# WRO_2025.net
KiCad netlist of a schematic drawn in EAGLE
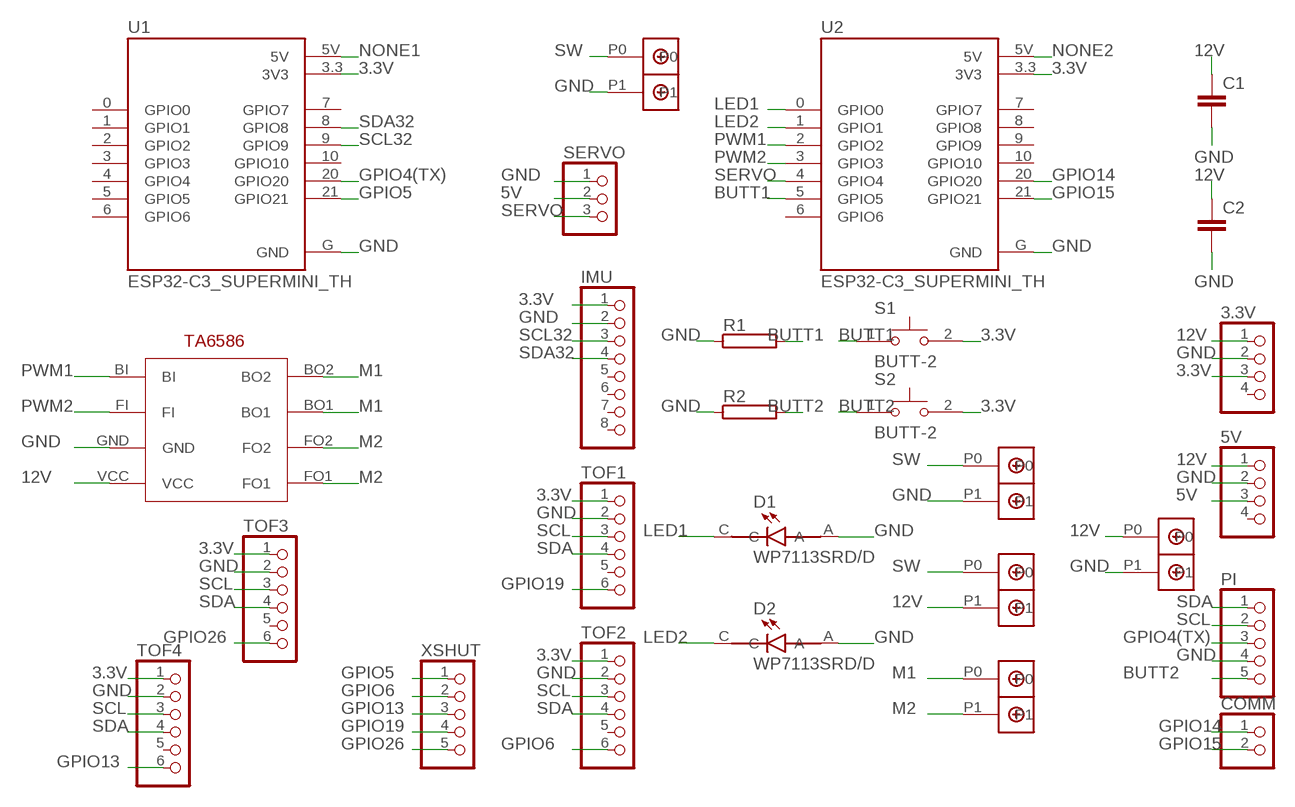
[diagram p0: schematic, sheet 1]

(export (version "E")
  (design (tool "Eeschema 10.0.6"))
  (components
    (comp (ref "3.3V")
      (value "PINHD-1X4")
      (footprint "eagle-import:1X04")
      (libsource (lib "eagle-import") (part "PINHD-1X4"))
    )
    (comp (ref "5V")
      (value "PINHD-1X4")
      (footprint "eagle-import:1X04")
      (libsource (lib "eagle-import") (part "PINHD-1X4"))
    )
    (comp (ref "C1")
      (value "C2,5-3")
      (footprint "eagle-import:C2.5-3")
      (libsource (lib "eagle-import") (part "C2,5-3"))
    )
    (comp (ref "C2")
      (value "C2,5-3")
      (footprint "eagle-import:C2.5-3")
      (libsource (lib "eagle-import") (part "C2,5-3"))
    )
    (comp (ref "COMM")
      (value "PINHD-1X2")
      (footprint "eagle-import:1X02")
      (libsource (lib "eagle-import") (part "PINHD-1X2"))
    )
    (comp (ref "D1")
      (value "WP7113SRD/D")
      (footprint "eagle-import:LED_WP7113SRD_D")
      (fields (field (name "MF") "Kingbright"))
      (libsource (lib "eagle-import") (part "WP7113SRD/D"))
    )
    (comp (ref "D2")
      (value "WP7113SRD/D")
      (footprint "eagle-import:LED_WP7113SRD_D")
      (fields (field (name "MF") "Kingbright"))
      (libsource (lib "eagle-import") (part "WP7113SRD/D"))
    )
    (comp (ref "IMU")
      (value "PINHD-1X8")
      (footprint "eagle-import:1X08")
      (libsource (lib "eagle-import") (part "PINHD-1X8"))
    )
    (comp (ref "PI")
      (value "PINHD-1X5")
      (footprint "eagle-import:1X05")
      (libsource (lib "eagle-import") (part "PINHD-1X5"))
    )
    (comp (ref "R1")
      (value "RHPS58")
      (footprint "eagle-import:HPS58")
      (libsource (lib "eagle-import") (part "RHPS58"))
    )
    (comp (ref "R2")
      (value "RHPS58")
      (footprint "eagle-import:HPS58")
      (libsource (lib "eagle-import") (part "RHPS58"))
    )
    (comp (ref "S1")
      (value "BUTT-2")
      (footprint "eagle-import:SW_BUTT-2")
      (fields (field (name "MF") "Gravitech"))
      (libsource (lib "eagle-import") (part "BUTT-2"))
    )
    (comp (ref "S2")
      (value "BUTT-2")
      (footprint "eagle-import:SW_BUTT-2")
      (fields (field (name "MF") "Gravitech"))
      (libsource (lib "eagle-import") (part "BUTT-2"))
    )
    (comp (ref "SERVO")
      (value "PINHD-1X3")
      (footprint "eagle-import:1X03")
      (libsource (lib "eagle-import") (part "PINHD-1X3"))
    )
    (comp (ref "TOF1")
      (value "PINHD-1X6")
      (footprint "eagle-import:1X06")
      (libsource (lib "eagle-import") (part "PINHD-1X6"))
    )
    (comp (ref "TOF2")
      (value "PINHD-1X6")
      (footprint "eagle-import:1X06")
      (libsource (lib "eagle-import") (part "PINHD-1X6"))
    )
    (comp (ref "TOF3")
      (value "PINHD-1X6")
      (footprint "eagle-import:1X06")
      (libsource (lib "eagle-import") (part "PINHD-1X6"))
    )
    (comp (ref "TOF4")
      (value "PINHD-1X6")
      (footprint "eagle-import:1X06")
      (libsource (lib "eagle-import") (part "PINHD-1X6"))
    )
    (comp (ref "U$1")
      (value "DBCONN-1X2")
      (footprint "eagle-import:DBCONN-1X2")
      (libsource (lib "eagle-import") (part "DBCONN-1X2"))
    )
    (comp (ref "U$2")
      (value "DBCONN-1X2")
      (footprint "eagle-import:DBCONN-1X2")
      (libsource (lib "eagle-import") (part "DBCONN-1X2"))
    )
    (comp (ref "U$3")
      (value "DBCONN-1X2")
      (footprint "eagle-import:DBCONN-1X2")
      (libsource (lib "eagle-import") (part "DBCONN-1X2"))
    )
    (comp (ref "U$4")
      (value "TA6586")
      (footprint "eagle-import:TA6586-FOOTPRINT")
      (fields (field (name "MF") "Wuxi"))
      (libsource (lib "eagle-import") (part "TA6586"))
    )
    (comp (ref "U$5")
      (value "DBCONN-1X2")
      (footprint "eagle-import:DBCONN-1X2")
      (libsource (lib "eagle-import") (part "DBCONN-1X2"))
    )
    (comp (ref "U$6")
      (value "DBCONN-1X2")
      (footprint "eagle-import:DBCONN-1X2")
      (libsource (lib "eagle-import") (part "DBCONN-1X2"))
    )
    (comp (ref "U1")
      (value "ESP32-C3_SUPERMINI_TH")
      (footprint "eagle-import:MODULE_ESP32-C3_SUPERMINI_TH")
      (fields (field (name "MF") "Espressif Systems") (field (name "MP") "ESP32-C3 SuperMini_TH"))
      (libsource (lib "eagle-import") (part "ESP32-C3_SUPERMINI_TH"))
    )
    (comp (ref "U2")
      (value "ESP32-C3_SUPERMINI_TH")
      (footprint "eagle-import:MODULE_ESP32-C3_SUPERMINI_TH")
      (fields (field (name "MF") "Espressif Systems") (field (name "MP") "ESP32-C3 SuperMini_TH"))
      (libsource (lib "eagle-import") (part "ESP32-C3_SUPERMINI_TH"))
    )
    (comp (ref "XSHUT")
      (value "PINHD-1X5")
      (footprint "eagle-import:1X05")
      (libsource (lib "eagle-import") (part "PINHD-1X5"))
    )
  )
  (nets
    (net (code "1") (name "/3.3V") (class "Default")
      (node (ref "3.3V") (pin "3") (pinfunction "3_3") (pintype "passive"))
      (node (ref "IMU") (pin "1") (pinfunction "1_1") (pintype "passive"))
      (node (ref "S1") (pin "2") (pinfunction "2_2") (pintype "passive"))
      (node (ref "S2") (pin "2") (pinfunction "2_2") (pintype "passive"))
      (node (ref "TOF1") (pin "1") (pinfunction "1_1") (pintype "passive"))
      (node (ref "TOF2") (pin "1") (pinfunction "1_1") (pintype "passive"))
      (node (ref "TOF3") (pin "1") (pinfunction "1_1") (pintype "passive"))
      (node (ref "TOF4") (pin "1") (pinfunction "1_1") (pintype "passive"))
      (node (ref "U1") (pin "3.3") (pinfunction "3V3_3.3") (pintype "power_in"))
      (node (ref "U2") (pin "3.3") (pinfunction "3V3_3.3") (pintype "power_in"))
    )
    (net (code "2") (name "/5V") (class "Default")
      (node (ref "5V") (pin "3") (pinfunction "3_3") (pintype "passive"))
      (node (ref "SERVO") (pin "2") (pinfunction "2_2") (pintype "passive"))
    )
    (net (code "3") (name "/12V") (class "Default")
      (node (ref "3.3V") (pin "1") (pinfunction "1_1") (pintype "passive"))
      (node (ref "5V") (pin "1") (pinfunction "1_1") (pintype "passive"))
      (node (ref "C1") (pin "1") (pinfunction "1_1") (pintype "passive"))
      (node (ref "C2") (pin "1") (pinfunction "1_1") (pintype "passive"))
      (node (ref "U$2") (pin "P1") (pinfunction "P1_P1") (pintype "bidirectional"))
      (node (ref "U$4") (pin "VCC") (pinfunction "VCC_VCC") (pintype "bidirectional"))
      (node (ref "U$5") (pin "P0") (pinfunction "P0_P0") (pintype "bidirectional"))
    )
    (net (code "4") (name "/BUTT1") (class "Default")
      (node (ref "R1") (pin "2") (pinfunction "2_2") (pintype "passive"))
      (node (ref "S1") (pin "1") (pinfunction "1_1") (pintype "passive"))
      (node (ref "U2") (pin "5") (pinfunction "GPIO5_5") (pintype "bidirectional"))
    )
    (net (code "5") (name "/BUTT2") (class "Default")
      (node (ref "PI") (pin "5") (pinfunction "5_5") (pintype "passive"))
      (node (ref "R2") (pin "2") (pinfunction "2_2") (pintype "passive"))
      (node (ref "S2") (pin "1") (pinfunction "1_1") (pintype "passive"))
    )
    (net (code "6") (name "/GND") (class "Default")
      (node (ref "3.3V") (pin "2") (pinfunction "2_2") (pintype "passive"))
      (node (ref "5V") (pin "2") (pinfunction "2_2") (pintype "passive"))
      (node (ref "C1") (pin "2") (pinfunction "2_2") (pintype "passive"))
      (node (ref "C2") (pin "2") (pinfunction "2_2") (pintype "passive"))
      (node (ref "D1") (pin "A") (pinfunction "A_A") (pintype "passive"))
      (node (ref "D2") (pin "A") (pinfunction "A_A") (pintype "passive"))
      (node (ref "IMU") (pin "2") (pinfunction "2_2") (pintype "passive"))
      (node (ref "PI") (pin "4") (pinfunction "4_4") (pintype "passive"))
      (node (ref "R1") (pin "1") (pinfunction "1_1") (pintype "passive"))
      (node (ref "R2") (pin "1") (pinfunction "1_1") (pintype "passive"))
      (node (ref "SERVO") (pin "1") (pinfunction "1_1") (pintype "passive"))
      (node (ref "TOF1") (pin "2") (pinfunction "2_2") (pintype "passive"))
      (node (ref "TOF2") (pin "2") (pinfunction "2_2") (pintype "passive"))
      (node (ref "TOF3") (pin "2") (pinfunction "2_2") (pintype "passive"))
      (node (ref "TOF4") (pin "2") (pinfunction "2_2") (pintype "passive"))
      (node (ref "U$1") (pin "P1") (pinfunction "P1_P1") (pintype "bidirectional"))
      (node (ref "U$4") (pin "GND") (pinfunction "GND_GND") (pintype "bidirectional"))
      (node (ref "U$5") (pin "P1") (pinfunction "P1_P1") (pintype "bidirectional"))
      (node (ref "U$6") (pin "P1") (pinfunction "P1_P1") (pintype "bidirectional"))
      (node (ref "U1") (pin "G") (pinfunction "GND_G") (pintype "power_in"))
      (node (ref "U2") (pin "G") (pinfunction "GND_G") (pintype "power_in"))
    )
    (net (code "7") (name "/GPIO4(TX)") (class "Default")
      (node (ref "PI") (pin "3") (pinfunction "3_3") (pintype "passive"))
      (node (ref "U1") (pin "20") (pinfunction "GPIO20_20") (pintype "bidirectional"))
    )
    (net (code "8") (name "/GPIO5") (class "Default")
      (node (ref "U1") (pin "21") (pinfunction "GPIO21_21") (pintype "bidirectional"))
      (node (ref "XSHUT") (pin "1") (pinfunction "1_1") (pintype "passive"))
    )
    (net (code "9") (name "/GPIO6") (class "Default")
      (node (ref "TOF2") (pin "6") (pinfunction "6_6") (pintype "passive"))
      (node (ref "XSHUT") (pin "2") (pinfunction "2_2") (pintype "passive"))
    )
    (net (code "10") (name "/GPIO13") (class "Default")
      (node (ref "TOF4") (pin "6") (pinfunction "6_6") (pintype "passive"))
      (node (ref "XSHUT") (pin "3") (pinfunction "3_3") (pintype "passive"))
    )
    (net (code "11") (name "/GPIO14") (class "Default")
      (node (ref "COMM") (pin "1") (pinfunction "1_1") (pintype "passive"))
      (node (ref "U2") (pin "20") (pinfunction "GPIO20_20") (pintype "bidirectional"))
    )
    (net (code "12") (name "/GPIO15") (class "Default")
      (node (ref "COMM") (pin "2") (pinfunction "2_2") (pintype "passive"))
      (node (ref "U2") (pin "21") (pinfunction "GPIO21_21") (pintype "bidirectional"))
    )
    (net (code "13") (name "/GPIO19") (class "Default")
      (node (ref "TOF1") (pin "6") (pinfunction "6_6") (pintype "passive"))
      (node (ref "XSHUT") (pin "4") (pinfunction "4_4") (pintype "passive"))
    )
    (net (code "14") (name "/GPIO26") (class "Default")
      (node (ref "TOF3") (pin "6") (pinfunction "6_6") (pintype "passive"))
      (node (ref "XSHUT") (pin "5") (pinfunction "5_5") (pintype "passive"))
    )
    (net (code "15") (name "/LED1") (class "Default")
      (node (ref "D1") (pin "C") (pinfunction "C_C") (pintype "passive"))
      (node (ref "U2") (pin "0") (pinfunction "GPIO0_0") (pintype "bidirectional"))
    )
    (net (code "16") (name "/LED2") (class "Default")
      (node (ref "D2") (pin "C") (pinfunction "C_C") (pintype "passive"))
      (node (ref "U2") (pin "1") (pinfunction "GPIO1_1") (pintype "bidirectional"))
    )
    (net (code "17") (name "/M1") (class "Default")
      (node (ref "U$3") (pin "P0") (pinfunction "P0_P0") (pintype "bidirectional"))
      (node (ref "U$4") (pin "BO1") (pinfunction "BO1_BO1") (pintype "bidirectional"))
      (node (ref "U$4") (pin "BO2") (pinfunction "BO2_BO2") (pintype "bidirectional"))
    )
    (net (code "18") (name "/M2") (class "Default")
      (node (ref "U$3") (pin "P1") (pinfunction "P1_P1") (pintype "bidirectional"))
      (node (ref "U$4") (pin "FO1") (pinfunction "FO1_FO1") (pintype "bidirectional"))
      (node (ref "U$4") (pin "FO2") (pinfunction "FO2_FO2") (pintype "bidirectional"))
    )
    (net (code "19") (name "/NONE1") (class "Default")
      (node (ref "U1") (pin "5V") (pinfunction "5V_5V") (pintype "power_in"))
    )
    (net (code "20") (name "/NONE2") (class "Default")
      (node (ref "U2") (pin "5V") (pinfunction "5V_5V") (pintype "power_in"))
    )
    (net (code "21") (name "/PWM1") (class "Default")
      (node (ref "U$4") (pin "BI") (pinfunction "BI_BI") (pintype "bidirectional"))
      (node (ref "U2") (pin "2") (pinfunction "GPIO2_2") (pintype "bidirectional"))
    )
    (net (code "22") (name "/PWM2") (class "Default")
      (node (ref "U$4") (pin "FI") (pinfunction "FI_FI") (pintype "bidirectional"))
      (node (ref "U2") (pin "3") (pinfunction "GPIO3_3") (pintype "bidirectional"))
    )
    (net (code "23") (name "/SCL") (class "Default")
      (node (ref "PI") (pin "2") (pinfunction "2_2") (pintype "passive"))
      (node (ref "TOF1") (pin "3") (pinfunction "3_3") (pintype "passive"))
      (node (ref "TOF2") (pin "3") (pinfunction "3_3") (pintype "passive"))
      (node (ref "TOF3") (pin "3") (pinfunction "3_3") (pintype "passive"))
      (node (ref "TOF4") (pin "3") (pinfunction "3_3") (pintype "passive"))
    )
    (net (code "24") (name "/SCL32") (class "Default")
      (node (ref "IMU") (pin "3") (pinfunction "3_3") (pintype "passive"))
      (node (ref "U1") (pin "9") (pinfunction "GPIO9_9") (pintype "bidirectional"))
    )
    (net (code "25") (name "/SDA") (class "Default")
      (node (ref "PI") (pin "1") (pinfunction "1_1") (pintype "passive"))
      (node (ref "TOF1") (pin "4") (pinfunction "4_4") (pintype "passive"))
      (node (ref "TOF2") (pin "4") (pinfunction "4_4") (pintype "passive"))
      (node (ref "TOF3") (pin "4") (pinfunction "4_4") (pintype "passive"))
      (node (ref "TOF4") (pin "4") (pinfunction "4_4") (pintype "passive"))
    )
    (net (code "26") (name "/SDA32") (class "Default")
      (node (ref "IMU") (pin "4") (pinfunction "4_4") (pintype "passive"))
      (node (ref "U1") (pin "8") (pinfunction "GPIO8_8") (pintype "bidirectional"))
    )
    (net (code "27") (name "/SERVO") (class "Default")
      (node (ref "SERVO") (pin "3") (pinfunction "3_3") (pintype "passive"))
      (node (ref "U2") (pin "4") (pinfunction "GPIO4_4") (pintype "bidirectional"))
    )
    (net (code "28") (name "/SW") (class "Default")
      (node (ref "U$1") (pin "P0") (pinfunction "P0_P0") (pintype "bidirectional"))
      (node (ref "U$2") (pin "P0") (pinfunction "P0_P0") (pintype "bidirectional"))
      (node (ref "U$6") (pin "P0") (pinfunction "P0_P0") (pintype "bidirectional"))
    )
    (net (code "29") (name "unconnected-(3.3V-Pad4)") (class "Default")
      (node (ref "3.3V") (pin "4") (pinfunction "4_4") (pintype "passive"))
    )
    (net (code "30") (name "unconnected-(5V-Pad4)") (class "Default")
      (node (ref "5V") (pin "4") (pinfunction "4_4") (pintype "passive"))
    )
    (net (code "31") (name "unconnected-(IMU-Pad5)") (class "Default")
      (node (ref "IMU") (pin "5") (pinfunction "5_5") (pintype "passive"))
    )
    (net (code "32") (name "unconnected-(IMU-Pad6)") (class "Default")
      (node (ref "IMU") (pin "6") (pinfunction "6_6") (pintype "passive"))
    )
    (net (code "33") (name "unconnected-(IMU-Pad7)") (class "Default")
      (node (ref "IMU") (pin "7") (pinfunction "7_7") (pintype "passive"))
    )
    (net (code "34") (name "unconnected-(IMU-Pad8)") (class "Default")
      (node (ref "IMU") (pin "8") (pinfunction "8_8") (pintype "passive"))
    )
    (net (code "35") (name "unconnected-(TOF1-Pad5)") (class "Default")
      (node (ref "TOF1") (pin "5") (pinfunction "5_5") (pintype "passive"))
    )
    (net (code "36") (name "unconnected-(TOF2-Pad5)") (class "Default")
      (node (ref "TOF2") (pin "5") (pinfunction "5_5") (pintype "passive"))
    )
    (net (code "37") (name "unconnected-(TOF3-Pad5)") (class "Default")
      (node (ref "TOF3") (pin "5") (pinfunction "5_5") (pintype "passive"))
    )
    (net (code "38") (name "unconnected-(TOF4-Pad5)") (class "Default")
      (node (ref "TOF4") (pin "5") (pinfunction "5_5") (pintype "passive"))
    )
    (net (code "39") (name "unconnected-(U1-GPIO0-Pad0)") (class "Default")
      (node (ref "U1") (pin "0") (pinfunction "GPIO0_0") (pintype "bidirectional"))
    )
    (net (code "40") (name "unconnected-(U1-GPIO1-Pad1)") (class "Default")
      (node (ref "U1") (pin "1") (pinfunction "GPIO1_1") (pintype "bidirectional"))
    )
    (net (code "41") (name "unconnected-(U1-GPIO2-Pad2)") (class "Default")
      (node (ref "U1") (pin "2") (pinfunction "GPIO2_2") (pintype "bidirectional"))
    )
    (net (code "42") (name "unconnected-(U1-GPIO3-Pad3)") (class "Default")
      (node (ref "U1") (pin "3") (pinfunction "GPIO3_3") (pintype "bidirectional"))
    )
    (net (code "43") (name "unconnected-(U1-GPIO4-Pad4)") (class "Default")
      (node (ref "U1") (pin "4") (pinfunction "GPIO4_4") (pintype "bidirectional"))
    )
    (net (code "44") (name "unconnected-(U1-GPIO5-Pad5)") (class "Default")
      (node (ref "U1") (pin "5") (pinfunction "GPIO5_5") (pintype "bidirectional"))
    )
    (net (code "45") (name "unconnected-(U1-GPIO6-Pad6)") (class "Default")
      (node (ref "U1") (pin "6") (pinfunction "GPIO6_6") (pintype "bidirectional"))
    )
    (net (code "46") (name "unconnected-(U1-GPIO7-Pad7)") (class "Default")
      (node (ref "U1") (pin "7") (pinfunction "GPIO7_7") (pintype "bidirectional"))
    )
    (net (code "47") (name "unconnected-(U1-GPIO10-Pad10)") (class "Default")
      (node (ref "U1") (pin "10") (pinfunction "GPIO10_10") (pintype "bidirectional"))
    )
    (net (code "48") (name "unconnected-(U2-GPIO6-Pad6)") (class "Default")
      (node (ref "U2") (pin "6") (pinfunction "GPIO6_6") (pintype "bidirectional"))
    )
    (net (code "49") (name "unconnected-(U2-GPIO7-Pad7)") (class "Default")
      (node (ref "U2") (pin "7") (pinfunction "GPIO7_7") (pintype "bidirectional"))
    )
    (net (code "50") (name "unconnected-(U2-GPIO8-Pad8)") (class "Default")
      (node (ref "U2") (pin "8") (pinfunction "GPIO8_8") (pintype "bidirectional"))
    )
    (net (code "51") (name "unconnected-(U2-GPIO9-Pad9)") (class "Default")
      (node (ref "U2") (pin "9") (pinfunction "GPIO9_9") (pintype "bidirectional"))
    )
    (net (code "52") (name "unconnected-(U2-GPIO10-Pad10)") (class "Default")
      (node (ref "U2") (pin "10") (pinfunction "GPIO10_10") (pintype "bidirectional"))
    )
  )
)
